# 5V_Reg.net
KiCad netlist of a schematic drawn in Altium Designer
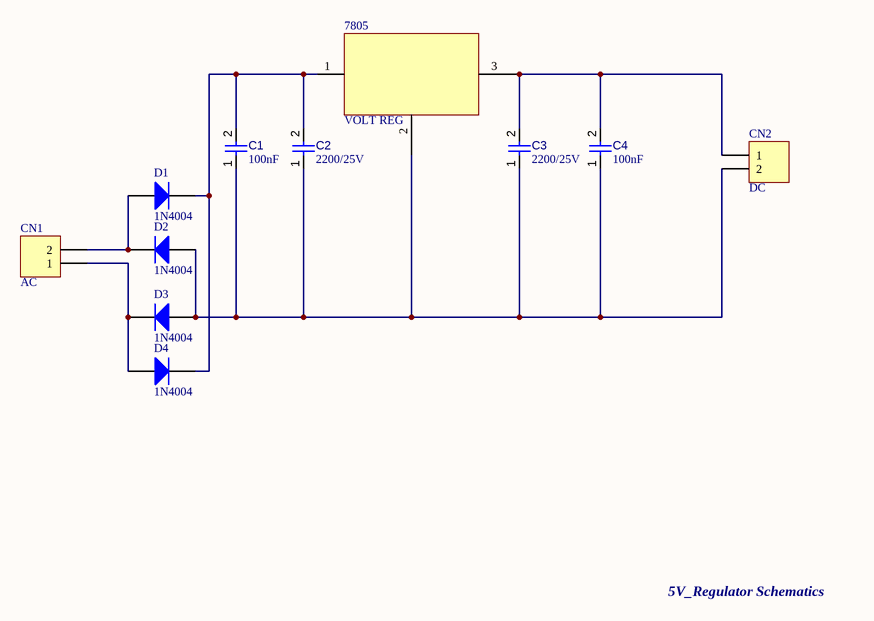
[diagram p0: 5V_Reg.SchDoc]

(export (version "E")
  (design (tool "Eeschema 10.0.6"))
  (components
    (comp (ref "7805")
      (value "VOLT REG")
      (footprint "PCBComponent_1")
      (libsource (lib "Integrated_Library1") (part "VOLT REG"))
    )
    (comp (ref "C1")
      (value "100nF")
      (footprint "CAPC0402(1005)60_L")
      (description "Chip Capacitor, 100nF +/-20%, 50V, 0402, Thickness 0.6 mm")
      (fields (field (name "TOLERANCE") "10%") (field (name "Comment") "Capacitor 100nF +/-20% 50V 0402"))
      (libsource (lib "Kashif Raza") (part "CAP-NP-2"))
    )
    (comp (ref "C2")
      (value "2200/25V")
      (footprint "CAPC0402(1005)60_L")
      (description "Chip Capacitor, 100nF +/-20%, 50V, 0402, Thickness 0.6 mm")
      (fields (field (name "TOLERANCE") "10%") (field (name "Comment") "Capacitor 100nF +/-20% 50V 0402"))
      (libsource (lib "Kashif Raza") (part "CAP-NP-2"))
    )
    (comp (ref "C3")
      (value "2200/25V")
      (footprint "CAPC0402(1005)60_L")
      (description "Chip Capacitor, 100nF +/-20%, 50V, 0402, Thickness 0.6 mm")
      (fields (field (name "TOLERANCE") "10%") (field (name "Comment") "Capacitor 100nF +/-20% 50V 0402"))
      (libsource (lib "Kashif Raza") (part "CAP-NP-2"))
    )
    (comp (ref "C4")
      (value "100nF")
      (footprint "CAPC0402(1005)60_L")
      (description "Chip Capacitor, 100nF +/-20%, 50V, 0402, Thickness 0.6 mm")
      (fields (field (name "TOLERANCE") "10%") (field (name "Comment") "Capacitor 100nF +/-20% 50V 0402"))
      (libsource (lib "Kashif Raza") (part "CAP-NP-2"))
    )
    (comp (ref "CN1")
      (value "AC")
      (footprint "MHDR1X2")
      (description "Header, 2-Pin")
      (fields (field (name "PUBLISHER") "Altium Limited"))
      (libsource (lib "Kashif Raza") (part "Header 2H"))
    )
    (comp (ref "CN2")
      (value "DC")
      (footprint "MHDR1X2")
      (description "Header, 2-Pin")
      (fields (field (name "PUBLISHER") "Altium Limited"))
      (libsource (lib "") (part "Header 2H_1"))
    )
    (comp (ref "D1")
      (value "1N4004")
      (footprint "FAIR-DO-41-2")
      (fields (field (name "MANUFACTURER") "Fairchild Semiconductor"))
      (libsource (lib "Kashif Raza") (part "D-AK-2"))
    )
    (comp (ref "D2")
      (value "1N4004")
      (footprint "FAIR-DO-41-2")
      (fields (field (name "MANUFACTURER") "Fairchild Semiconductor"))
      (libsource (lib "Kashif Raza") (part "D-AK-2"))
    )
    (comp (ref "D3")
      (value "1N4004")
      (footprint "FAIR-DO-41-2")
      (fields (field (name "MANUFACTURER") "Fairchild Semiconductor"))
      (libsource (lib "Kashif Raza") (part "D-AK-2"))
    )
    (comp (ref "D4")
      (value "1N4004")
      (footprint "FAIR-DO-41-2")
      (fields (field (name "MANUFACTURER") "Fairchild Semiconductor"))
      (libsource (lib "Kashif Raza") (part "D-AK-2"))
    )
  )
  (nets
    (net (code "1") (name "Net-(7805-Pad3)") (class "Default")
      (node (ref "7805") (pin "3") (pintype "passive"))
      (node (ref "C3") (pin "2") (pinfunction "2_2") (pintype "passive"))
      (node (ref "C4") (pin "2") (pinfunction "2_2") (pintype "passive"))
      (node (ref "CN2") (pin "1") (pinfunction "1_1") (pintype "passive"))
    )
    (net (code "2") (name "Net-(D1-A)") (class "Default")
      (node (ref "CN1") (pin "2") (pinfunction "2_2") (pintype "passive"))
      (node (ref "D1") (pin "1") (pinfunction "A_1") (pintype "passive"))
      (node (ref "D2") (pin "2") (pinfunction "K_2") (pintype "passive"))
    )
    (net (code "3") (name "Net-(D1-K)") (class "Default")
      (node (ref "7805") (pin "1") (pintype "passive"))
      (node (ref "C1") (pin "2") (pinfunction "2_2") (pintype "passive"))
      (node (ref "C2") (pin "2") (pinfunction "2_2") (pintype "passive"))
      (node (ref "D1") (pin "2") (pinfunction "K_2") (pintype "passive"))
      (node (ref "D4") (pin "2") (pinfunction "K_2") (pintype "passive"))
    )
    (net (code "4") (name "Net-(D2-A)") (class "Default")
      (node (ref "7805") (pin "2") (pintype "passive"))
      (node (ref "C1") (pin "1") (pinfunction "1_1") (pintype "passive"))
      (node (ref "C2") (pin "1") (pinfunction "1_1") (pintype "passive"))
      (node (ref "C3") (pin "1") (pinfunction "1_1") (pintype "passive"))
      (node (ref "C4") (pin "1") (pinfunction "1_1") (pintype "passive"))
      (node (ref "CN2") (pin "2") (pinfunction "2_2") (pintype "passive"))
      (node (ref "D2") (pin "1") (pinfunction "A_1") (pintype "passive"))
      (node (ref "D3") (pin "1") (pinfunction "A_1") (pintype "passive"))
    )
    (net (code "5") (name "Net-(D3-K)") (class "Default")
      (node (ref "CN1") (pin "1") (pinfunction "1_1") (pintype "passive"))
      (node (ref "D3") (pin "2") (pinfunction "K_2") (pintype "passive"))
      (node (ref "D4") (pin "1") (pinfunction "A_1") (pintype "passive"))
    )
  )
)
